# TELM0003_TempSense.net
KiCad netlist of a schematic drawn in Altium Designer
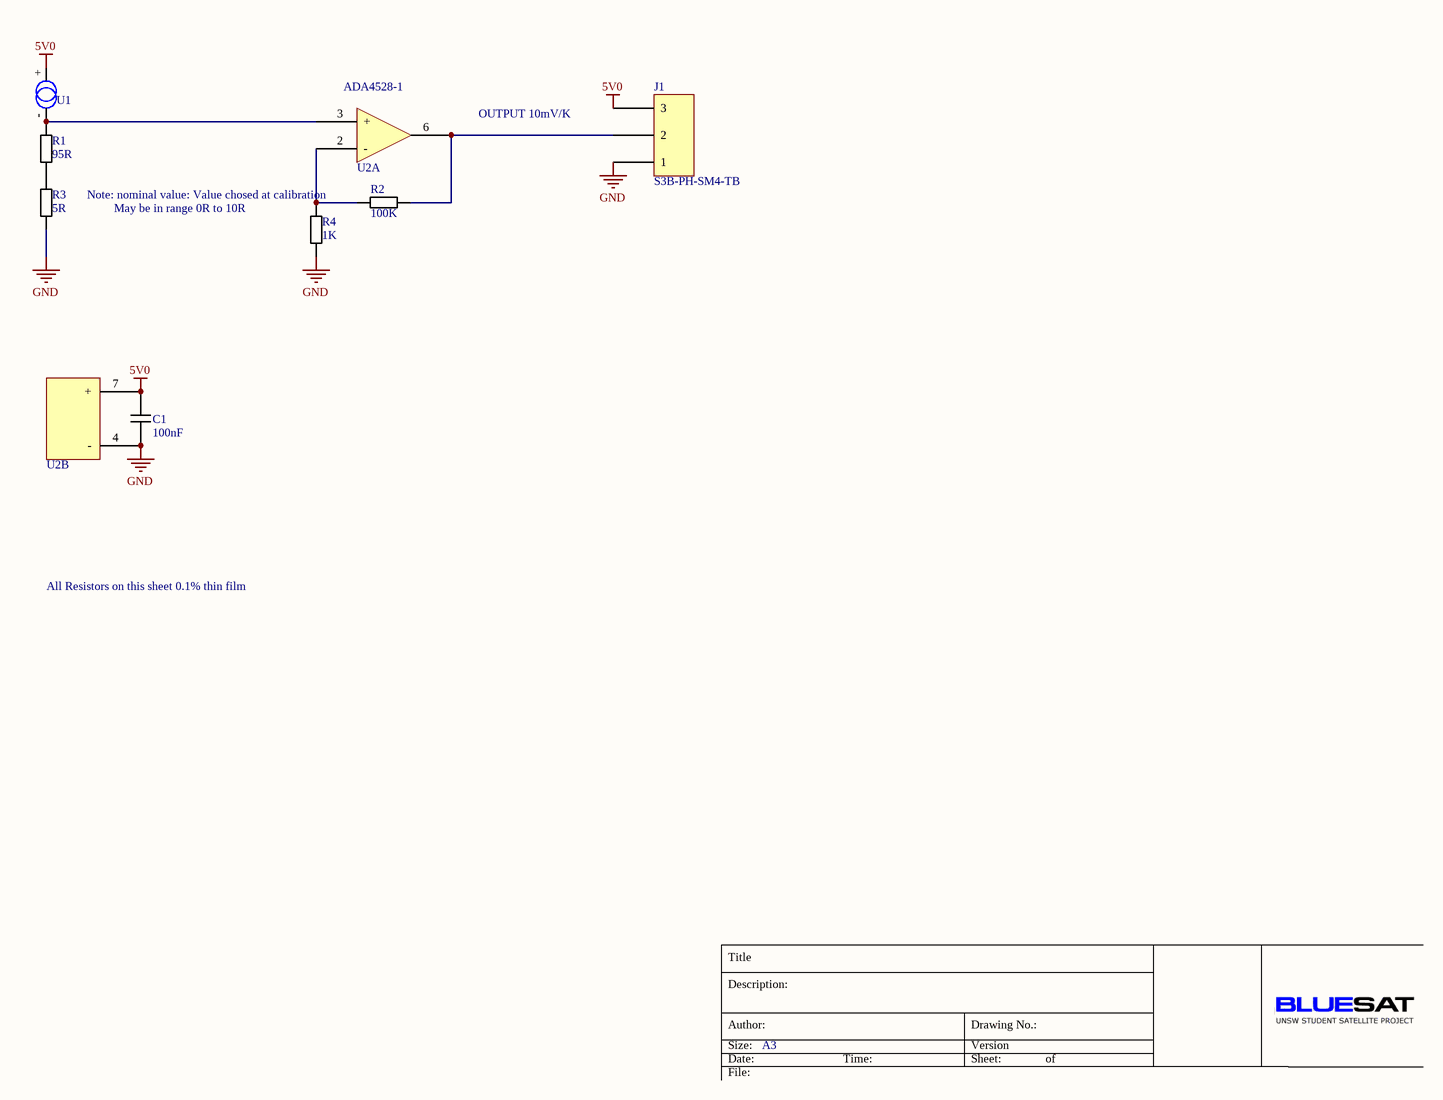
[diagram p0: TELM0003_TempSense.SchDoc]

(export (version "E")
  (design (tool "Eeschema 10.0.6"))
  (components
    (comp (ref "C1")
      (value "100nF")
      (footprint "1206 Cap")
      (description "1206 MLCC - X7R, 10%")
      (fields (field (name "Comment") "1206 Cap"))
      (libsource (lib "Schlib1") (part "1206 MLCC - X7R, 10%"))
    )
    (comp (ref "J1")
      (value "S3B-PH-SM4-TB")
      (footprint "S3B-PH-SM4-TB")
      (description "JST connector")
      (libsource (lib "Schlib1") (part "S3B-PH-SM4-TB"))
    )
    (comp (ref "R1")
      (value "95R")
      (footprint "0603 Resistor")
      (description "0603 Thin Film Resistor 0.1%")
      (fields (field (name "Comment") "0603 Resistor"))
      (libsource (lib "Schlib1") (part "0603 Thin Film Resistor 0.1%"))
    )
    (comp (ref "R2")
      (value "100K")
      (footprint "0603 Resistor")
      (description "0603 Thin Film Resistor 0.1%")
      (fields (field (name "Comment") "0603 Resistor"))
      (libsource (lib "") (part "0603 Thin Film Resistor 0.1%_1"))
    )
    (comp (ref "R3")
      (value "5R")
      (footprint "0603 Resistor")
      (description "0603 Thin Film Resistor 0.1%")
      (fields (field (name "Comment") "0603 Resistor"))
      (libsource (lib "Schlib1") (part "0603 Thin Film Resistor 0.1%"))
    )
    (comp (ref "R4")
      (value "1K")
      (footprint "0603 Resistor")
      (description "0603 Thin Film Resistor 0.1%")
      (fields (field (name "Comment") "0603 Resistor"))
      (libsource (lib "Schlib1") (part "0603 Thin Film Resistor 0.1%"))
    )
    (comp (ref "U1")
      (value "AD590KF")
      (footprint "5.05mm Terminal Block - 2")
      (description "Temperature sensor IC")
      (libsource (lib "Schlib1") (part "AD590KF"))
    )
    (comp (ref "U2")
      (value "ADA4528-1")
      (footprint "SOIC8 - LME49720")
      (description "Dual, High Performance Audio Operational Amplifier")
      (libsource (lib "") (part "ADA4528-1_1"))
    )
  )
  (nets
    (net (code "1") (name "5V0") (class "Default")
      (node (ref "C1") (pin "2") (pinfunction "2_2") (pintype "passive"))
      (node (ref "J1") (pin "3") (pinfunction "3_3") (pintype "passive"))
      (node (ref "U1") (pin "+") (pinfunction "+_+") (pintype "passive"))
      (node (ref "U2") (pin "7") (pinfunction "+_7") (pintype "power_in"))
    )
    (net (code "2") (name "GND") (class "Default")
      (node (ref "C1") (pin "1") (pinfunction "1_1") (pintype "passive"))
      (node (ref "J1") (pin "1") (pinfunction "1_1") (pintype "passive"))
      (node (ref "R3") (pin "1") (pinfunction "1_1") (pintype "passive"))
      (node (ref "R4") (pin "1") (pinfunction "1_1") (pintype "passive"))
      (node (ref "U2") (pin "4") (pinfunction "-_4") (pintype "power_in"))
    )
    (net (code "3") (name "Net-(R1-Pad1)") (class "Default")
      (node (ref "R1") (pin "1") (pinfunction "1_1") (pintype "passive"))
      (node (ref "R3") (pin "2") (pinfunction "2_2") (pintype "passive"))
    )
    (net (code "4") (name "Net-(U2A-+)") (class "Default")
      (node (ref "R1") (pin "2") (pinfunction "2_2") (pintype "passive"))
      (node (ref "U1") (pin "-") (pinfunction "-_-") (pintype "passive"))
      (node (ref "U2") (pin "3") (pinfunction "+_3") (pintype "passive"))
    )
    (net (code "5") (name "Net-(U2A--)") (class "Default")
      (node (ref "R2") (pin "2") (pinfunction "2_2") (pintype "passive"))
      (node (ref "R4") (pin "2") (pinfunction "2_2") (pintype "passive"))
      (node (ref "U2") (pin "2") (pinfunction "-_2") (pintype "passive"))
    )
    (net (code "6") (name "Net-(U2A-Out)") (class "Default")
      (node (ref "J1") (pin "2") (pinfunction "2_2") (pintype "passive"))
      (node (ref "R2") (pin "1") (pinfunction "1_1") (pintype "passive"))
      (node (ref "U2") (pin "6") (pinfunction "Out_6") (pintype "passive"))
    )
  )
)
